# balance_stm32.net
KiCad netlist of a schematic drawn in EasyEDA Pro
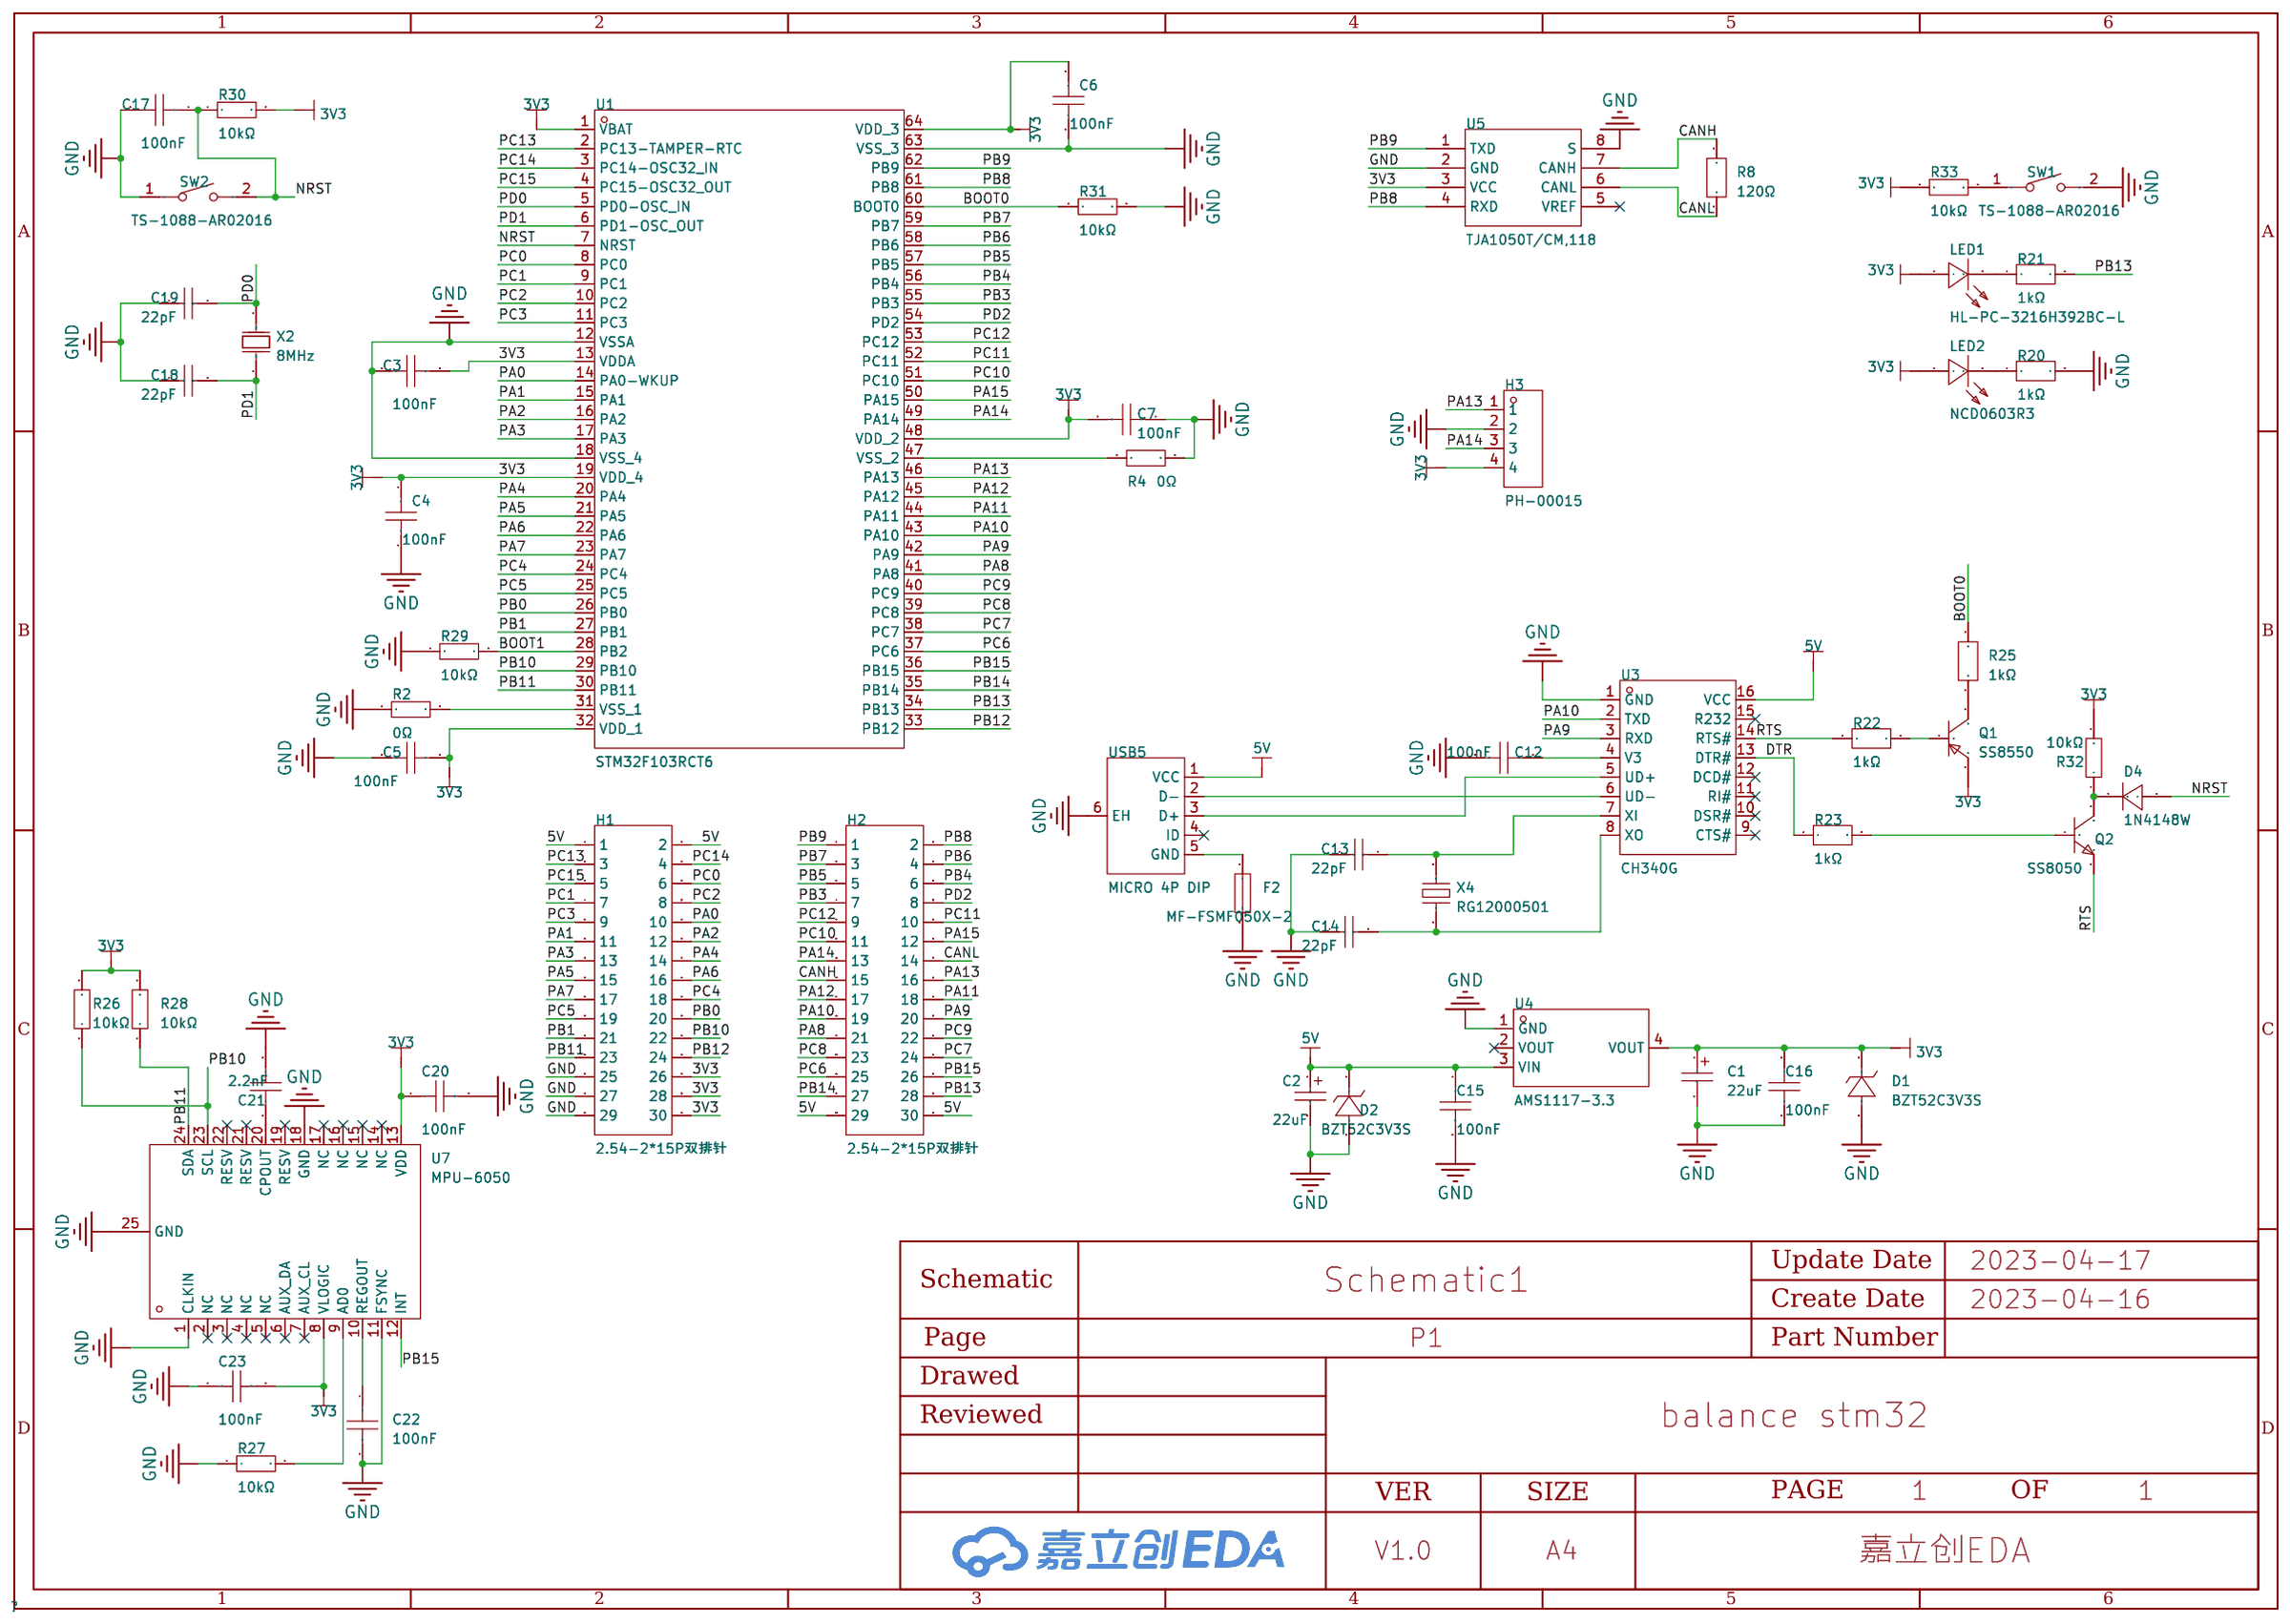
[diagram p0: schematic sheet]

(export (version "E")
  (design (tool "Eeschema 10.0.6"))
  (components
    (comp (ref "C1")
      (value "22uF")
      (footprint "easyedapro:CAP-SMD_L7.3-W4.3-RD")
      (description "容值:22uF;精度:±10%;额定电压:35V;等效串联电阻:900mΩ@100kHz;")
      (fields (field (name "Manufacturer Part") "TAJD226K035RNJ") (field (name "Manufacturer") "Kyocera AVX"))
      (libsource (lib "easyedapro") (part "TAJD226K035RNJ"))
    )
    (comp (ref "C2")
      (value "22uF")
      (footprint "easyedapro:CAP-SMD_L7.3-W4.3-RD")
      (description "容值:22uF;精度:±10%;额定电压:35V;等效串联电阻:900mΩ@100kHz;")
      (fields (field (name "Manufacturer Part") "TAJD226K035RNJ") (field (name "Manufacturer") "Kyocera AVX"))
      (libsource (lib "easyedapro") (part "TAJD226K035RNJ"))
    )
    (comp (ref "C3")
      (value "100nF")
      (footprint "easyedapro:C0603")
      (description "容值:100nF;精度:±10%;额定电压:50V;材质(温度系数):X7R;")
      (fields
        (field (name "Manufacturer Part") "CL10B104KB8NNNC")
        (field (name "Manufacturer") "SAMSUNG(三星)")
      )
      (libsource (lib "easyedapro") (part "CL10B104KB8NNNC"))
    )
    (comp (ref "C4")
      (value "100nF")
      (footprint "easyedapro:C0603")
      (description "容值:100nF;精度:±10%;额定电压:50V;材质(温度系数):X7R;")
      (fields
        (field (name "Manufacturer Part") "CL10B104KB8NNNC")
        (field (name "Manufacturer") "SAMSUNG(三星)")
      )
      (libsource (lib "easyedapro") (part "CL10B104KB8NNNC"))
    )
    (comp (ref "C5")
      (value "100nF")
      (footprint "easyedapro:C0603")
      (description "容值:100nF;精度:±10%;额定电压:50V;材质(温度系数):X7R;")
      (fields
        (field (name "Manufacturer Part") "CL10B104KB8NNNC")
        (field (name "Manufacturer") "SAMSUNG(三星)")
      )
      (libsource (lib "easyedapro") (part "CL10B104KB8NNNC"))
    )
    (comp (ref "C6")
      (value "100nF")
      (footprint "easyedapro:C0603")
      (description "容值:100nF;精度:±10%;额定电压:50V;材质(温度系数):X7R;")
      (fields
        (field (name "Manufacturer Part") "CL10B104KB8NNNC")
        (field (name "Manufacturer") "SAMSUNG(三星)")
      )
      (libsource (lib "easyedapro") (part "CL10B104KB8NNNC"))
    )
    (comp (ref "C7")
      (value "100nF")
      (footprint "easyedapro:C0603")
      (description "容值:100nF;精度:±10%;额定电压:50V;材质(温度系数):X7R;")
      (fields
        (field (name "Manufacturer Part") "CL10B104KB8NNNC")
        (field (name "Manufacturer") "SAMSUNG(三星)")
      )
      (libsource (lib "easyedapro") (part "CL10B104KB8NNNC"))
    )
    (comp (ref "C12")
      (value "100nF")
      (footprint "easyedapro:C0603")
      (description "容值:100nF;精度:±10%;额定电压:50V;材质(温度系数):X7R;")
      (fields
        (field (name "Manufacturer Part") "CL10B104KB8NNNC")
        (field (name "Manufacturer") "SAMSUNG(三星)")
      )
      (libsource (lib "easyedapro") (part "CL10B104KB8NNNC"))
    )
    (comp (ref "C13")
      (value "22pF")
      (footprint "easyedapro:C0603")
      (description "容值:22pF;精度:±5%;额定电压:50V;材质(温度系数):C0G;")
      (fields
        (field (name "Manufacturer Part") "CL10C220JB8NNNC")
        (field (name "Manufacturer") "SAMSUNG(三星)")
      )
      (libsource (lib "easyedapro") (part "CL10C220JB8NNNC"))
    )
    (comp (ref "C14")
      (value "22pF")
      (footprint "easyedapro:C0603")
      (description "容值:22pF;精度:±5%;额定电压:50V;材质(温度系数):C0G;")
      (fields
        (field (name "Manufacturer Part") "CL10C220JB8NNNC")
        (field (name "Manufacturer") "SAMSUNG(三星)")
      )
      (libsource (lib "easyedapro") (part "CL10C220JB8NNNC"))
    )
    (comp (ref "C15")
      (value "100nF")
      (footprint "easyedapro:C0603")
      (description "容值:100nF;精度:±10%;额定电压:50V;材质(温度系数):X7R;")
      (fields
        (field (name "Manufacturer Part") "CL10B104KB8NNNC")
        (field (name "Manufacturer") "SAMSUNG(三星)")
      )
      (libsource (lib "easyedapro") (part "CL10B104KB8NNNC"))
    )
    (comp (ref "C16")
      (value "100nF")
      (footprint "easyedapro:C0603")
      (description "容值:100nF;精度:±10%;额定电压:50V;材质(温度系数):X7R;")
      (fields
        (field (name "Manufacturer Part") "CL10B104KB8NNNC")
        (field (name "Manufacturer") "SAMSUNG(三星)")
      )
      (libsource (lib "easyedapro") (part "CL10B104KB8NNNC"))
    )
    (comp (ref "C17")
      (value "100nF")
      (footprint "easyedapro:C0603")
      (description "容值:100nF;精度:±10%;额定电压:50V;材质(温度系数):X7R;")
      (fields
        (field (name "Manufacturer Part") "CL10B104KB8NNNC")
        (field (name "Manufacturer") "SAMSUNG(三星)")
      )
      (libsource (lib "easyedapro") (part "CL10B104KB8NNNC"))
    )
    (comp (ref "C18")
      (value "22pF")
      (footprint "easyedapro:C0603")
      (description "容值:22pF;精度:±5%;额定电压:50V;材质(温度系数):C0G;")
      (fields
        (field (name "Manufacturer Part") "CL10C220JB8NNNC")
        (field (name "Manufacturer") "SAMSUNG(三星)")
      )
      (libsource (lib "easyedapro") (part "CL10C220JB8NNNC"))
    )
    (comp (ref "C19")
      (value "22pF")
      (footprint "easyedapro:C0603")
      (description "容值:22pF;精度:±5%;额定电压:50V;材质(温度系数):C0G;")
      (fields
        (field (name "Manufacturer Part") "CL10C220JB8NNNC")
        (field (name "Manufacturer") "SAMSUNG(三星)")
      )
      (libsource (lib "easyedapro") (part "CL10C220JB8NNNC"))
    )
    (comp (ref "C20")
      (value "100nF")
      (footprint "easyedapro:C0603")
      (description "容值:100nF;精度:±10%;额定电压:50V;材质(温度系数):X7R;")
      (fields
        (field (name "Manufacturer Part") "CL10B104KB8NNNC")
        (field (name "Manufacturer") "SAMSUNG(三星)")
      )
      (libsource (lib "easyedapro") (part "CL10B104KB8NNNC"))
    )
    (comp (ref "C21")
      (value "2.2nF")
      (footprint "easyedapro:C0603")
      (description "容值:2.2nF;精度:±5%;额定电压:250V;材质(温度系数):C0G;")
      (fields (field (name "Manufacturer Part") "C1608C0G2E222JT000N") (field (name "Manufacturer") "TDK"))
      (libsource (lib "easyedapro") (part "C1608C0G2E222JT000N"))
    )
    (comp (ref "C22")
      (value "100nF")
      (footprint "easyedapro:C0603")
      (description "容值:100nF;精度:±10%;额定电压:50V;材质(温度系数):X7R;")
      (fields
        (field (name "Manufacturer Part") "CL10B104KB8NNNC")
        (field (name "Manufacturer") "SAMSUNG(三星)")
      )
      (libsource (lib "easyedapro") (part "CL10B104KB8NNNC"))
    )
    (comp (ref "C23")
      (value "100nF")
      (footprint "easyedapro:C0603")
      (description "容值:100nF;精度:±10%;额定电压:50V;材质(温度系数):X7R;")
      (fields
        (field (name "Manufacturer Part") "CL10B104KB8NNNC")
        (field (name "Manufacturer") "SAMSUNG(三星)")
      )
      (libsource (lib "easyedapro") (part "CL10B104KB8NNNC"))
    )
    (comp (ref "D1")
      (value "BZT52C3V3S")
      (footprint "easyedapro:SOD-323_L1.7-W1.3-LS2.6-RD-1")
      (description "二极管配置:-;稳压值(标称值):3.3V;稳压值(范围):3.3V~3.5V;功率:200mW;反向电流(Ir):5uA@1V;阻抗(Zzt):95Ω;")
      (fields (field (name "Manufacturer") "YONGYUTAI(永裕泰)"))
      (libsource (lib "easyedapro") (part "BZT52C3V3S_C2892655"))
    )
    (comp (ref "D2")
      (value "BZT52C3V3S")
      (footprint "easyedapro:SOD-323_L1.7-W1.3-LS2.6-RD-1")
      (description "二极管配置:-;稳压值(标称值):3.3V;稳压值(范围):3.3V~3.5V;功率:200mW;反向电流(Ir):5uA@1V;阻抗(Zzt):95Ω;")
      (fields (field (name "Manufacturer") "YONGYUTAI(永裕泰)"))
      (libsource (lib "easyedapro") (part "BZT52C3V3S_C2892655"))
    )
    (comp (ref "D4")
      (value "1N4148W")
      (footprint "easyedapro:SOD-123_L2.8-W1.8-LS3.7-RD")
      (fields (field (name "Manufacturer") "Slkor(萨科微)"))
      (libsource (lib "easyedapro") (part "1N4148W_C444720"))
    )
    (comp (ref "F2")
      (value "MF-FSMF050X-2")
      (footprint "easyedapro:F0603")
      (fields (field (name "Manufacturer") "BOURNS"))
      (libsource (lib "easyedapro") (part "MF-FSMF050X-2"))
    )
    (comp (ref "H1")
      (value "2.54-2*15P双排针")
      (footprint "easyedapro:HDR-TH_30P-P2.54-V-M-R2-C15-S2.54")
      (fields (field (name "Manufacturer") "BOOMELE(博穆精密)"))
      (libsource (lib "easyedapro") (part "Header-Male-2.54_2x15"))
    )
    (comp (ref "H2")
      (value "2.54-2*15P双排针")
      (footprint "easyedapro:HDR-TH_30P-P2.54-V-M-R2-C15-S2.54")
      (fields (field (name "Manufacturer") "BOOMELE(博穆精密)"))
      (libsource (lib "easyedapro") (part "Header-Male-2.54_2x15"))
    )
    (comp (ref "H3")
      (value "PH-00015")
      (footprint "easyedapro:HDR-TH_4P-P2.54-V-M")
      (fields (field (name "Manufacturer") "Liansheng(连盛)"))
      (libsource (lib "easyedapro") (part "PH-00015"))
    )
    (comp (ref "LED1")
      (value "HL-PC-3216H392BC-L")
      (footprint "easyedapro:LED1206-R-RD_BLUE")
      (fields (field (name "Manufacturer") "HONGLITRONIC(鸿利光电)"))
      (libsource (lib "easyedapro") (part "HL-PC-3216H392BC-L"))
    )
    (comp (ref "LED2")
      (value "NCD0603R3")
      (footprint "easyedapro:LED0603-R-RD_RED")
      (description "尺寸1.6x0.8x0.8；IF=20ma：1.6~2.6v，620~640nm,51~150mcd金线，光强高，功耗低，可靠性好，寿命长")
      (fields (field (name "Manufacturer") "国星光电"))
      (libsource (lib "easyedapro") (part "NCD0603R3"))
    )
    (comp (ref "Q1")
      (value "SS8550")
      (footprint "easyedapro:SOT-23-3_L2.9-W1.3-P1.90-LS2.4-BR")
      (fields (field (name "Manufacturer") "FUXINSEMI(富芯森美)"))
      (libsource (lib "easyedapro") (part "SS8550_C908251"))
    )
    (comp (ref "Q2")
      (value "SS8050")
      (footprint "easyedapro:SOT-23-3_L2.9-W1.3-P1.90-LS2.4-BR")
      (fields (field (name "Manufacturer") "FUXINSEMI(富芯森美)"))
      (libsource (lib "easyedapro") (part "SS8050"))
    )
    (comp (ref "R2")
      (value "0Ω")
      (footprint "easyedapro:R0603")
      (description "电阻类型:厚膜电阻;阻值:0Ω;精度:-;功率:250mW;")
      (fields (field (name "Manufacturer Part") "PMR03EZPJ000") (field (name "Manufacturer") "ROHM(罗姆)"))
      (libsource (lib "easyedapro") (part "PMR03EZPJ000"))
    )
    (comp (ref "R4")
      (value "0Ω")
      (footprint "easyedapro:R0603")
      (description "电阻类型:厚膜电阻;阻值:0Ω;精度:-;功率:250mW;")
      (fields (field (name "Manufacturer Part") "PMR03EZPJ000") (field (name "Manufacturer") "ROHM(罗姆)"))
      (libsource (lib "easyedapro") (part "PMR03EZPJ000"))
    )
    (comp (ref "R8")
      (value "120Ω")
      (footprint "easyedapro:R0805")
      (description "电阻类型:薄膜电阻;阻值:120Ω;精度:±0.1%;功率:200mW;")
      (fields
        (field (name "Manufacturer Part") "RTAN0805BKE120R")
        (field (name "Manufacturer") "SEI(Stackpole Electronics Inc.)")
      )
      (libsource (lib "easyedapro") (part "RTAN0805BKE120R"))
    )
    (comp (ref "R20")
      (value "1kΩ")
      (footprint "easyedapro:R0603")
      (description "电阻类型:薄膜电阻;阻值:1kΩ;精度:±0.1%;功率:100mW;")
      (fields (field (name "Manufacturer Part") "ERA3VEB1001V") (field (name "Manufacturer") "PANASONIC(松下)"))
      (libsource (lib "easyedapro") (part "ERA3VEB1001V"))
    )
    (comp (ref "R21")
      (value "1kΩ")
      (footprint "easyedapro:R0603")
      (description "电阻类型:薄膜电阻;阻值:1kΩ;精度:±0.1%;功率:100mW;")
      (fields (field (name "Manufacturer Part") "ERA3VEB1001V") (field (name "Manufacturer") "PANASONIC(松下)"))
      (libsource (lib "easyedapro") (part "ERA3VEB1001V"))
    )
    (comp (ref "R22")
      (value "1kΩ")
      (footprint "easyedapro:R0603")
      (description "电阻类型:薄膜电阻;阻值:1kΩ;精度:±0.1%;功率:100mW;")
      (fields (field (name "Manufacturer Part") "ERA3VEB1001V") (field (name "Manufacturer") "PANASONIC(松下)"))
      (libsource (lib "easyedapro") (part "ERA3VEB1001V"))
    )
    (comp (ref "R23")
      (value "1kΩ")
      (footprint "easyedapro:R0603")
      (description "电阻类型:薄膜电阻;阻值:1kΩ;精度:±0.1%;功率:100mW;")
      (fields (field (name "Manufacturer Part") "ERA3VEB1001V") (field (name "Manufacturer") "PANASONIC(松下)"))
      (libsource (lib "easyedapro") (part "ERA3VEB1001V"))
    )
    (comp (ref "R25")
      (value "1kΩ")
      (footprint "easyedapro:R0603")
      (description "电阻类型:薄膜电阻;阻值:1kΩ;精度:±0.1%;功率:100mW;")
      (fields (field (name "Manufacturer Part") "ERA3VEB1001V") (field (name "Manufacturer") "PANASONIC(松下)"))
      (libsource (lib "easyedapro") (part "ERA3VEB1001V"))
    )
    (comp (ref "R26")
      (value "10kΩ")
      (footprint "easyedapro:R0603")
      (description "电阻类型:厚膜电阻;阻值:10kΩ;精度:±0.1%;功率:200mW;")
      (fields (field (name "Manufacturer Part") "ERJPB3B1002V") (field (name "Manufacturer") "PANASONIC(松下)"))
      (libsource (lib "easyedapro") (part "ERJPB3B1002V"))
    )
    (comp (ref "R27")
      (value "10kΩ")
      (footprint "easyedapro:R0603")
      (description "电阻类型:厚膜电阻;阻值:10kΩ;精度:±0.1%;功率:200mW;")
      (fields (field (name "Manufacturer Part") "ERJPB3B1002V") (field (name "Manufacturer") "PANASONIC(松下)"))
      (libsource (lib "easyedapro") (part "ERJPB3B1002V"))
    )
    (comp (ref "R28")
      (value "10kΩ")
      (footprint "easyedapro:R0603")
      (description "电阻类型:厚膜电阻;阻值:10kΩ;精度:±0.1%;功率:200mW;")
      (fields (field (name "Manufacturer Part") "ERJPB3B1002V") (field (name "Manufacturer") "PANASONIC(松下)"))
      (libsource (lib "easyedapro") (part "ERJPB3B1002V"))
    )
    (comp (ref "R29")
      (value "10kΩ")
      (footprint "easyedapro:R0603")
      (description "电阻类型:厚膜电阻;阻值:10kΩ;精度:±0.1%;功率:200mW;")
      (fields (field (name "Manufacturer Part") "ERJPB3B1002V") (field (name "Manufacturer") "PANASONIC(松下)"))
      (libsource (lib "easyedapro") (part "ERJPB3B1002V"))
    )
    (comp (ref "R30")
      (value "10kΩ")
      (footprint "easyedapro:R0603")
      (description "电阻类型:厚膜电阻;阻值:10kΩ;精度:±0.1%;功率:200mW;")
      (fields (field (name "Manufacturer Part") "ERJPB3B1002V") (field (name "Manufacturer") "PANASONIC(松下)"))
      (libsource (lib "easyedapro") (part "ERJPB3B1002V"))
    )
    (comp (ref "R31")
      (value "10kΩ")
      (footprint "easyedapro:R0603")
      (description "电阻类型:厚膜电阻;阻值:10kΩ;精度:±0.1%;功率:200mW;")
      (fields (field (name "Manufacturer Part") "ERJPB3B1002V") (field (name "Manufacturer") "PANASONIC(松下)"))
      (libsource (lib "easyedapro") (part "ERJPB3B1002V"))
    )
    (comp (ref "R32")
      (value "10kΩ")
      (footprint "easyedapro:R0603")
      (description "电阻类型:厚膜电阻;阻值:10kΩ;精度:±0.1%;功率:200mW;")
      (fields (field (name "Manufacturer Part") "ERJPB3B1002V") (field (name "Manufacturer") "PANASONIC(松下)"))
      (libsource (lib "easyedapro") (part "ERJPB3B1002V"))
    )
    (comp (ref "R33")
      (value "10kΩ")
      (footprint "easyedapro:R0603")
      (description "电阻类型:厚膜电阻;阻值:10kΩ;精度:±0.1%;功率:200mW;")
      (fields (field (name "Manufacturer Part") "ERJPB3B1002V") (field (name "Manufacturer") "PANASONIC(松下)"))
      (libsource (lib "easyedapro") (part "ERJPB3B1002V"))
    )
    (comp (ref "SW1")
      (value "TS-1088-AR02016")
      (footprint "easyedapro:SW-SMD_L3.9-W3.0-P4.45")
      (description "触点电流:50mA;额定电压(DC):12V;绝缘电阻:100MΩ;电路结构:单刀单掷;安装方式:立贴;作用力:160gf@±50gf;机械寿命:10万次;带支架:否;")
      (fields (field (name "Manufacturer") "XUNPU(讯普)"))
      (libsource (lib "easyedapro") (part "TS-1088-AR02016"))
    )
    (comp (ref "SW2")
      (value "TS-1088-AR02016")
      (footprint "easyedapro:SW-SMD_L3.9-W3.0-P4.45")
      (description "触点电流:50mA;额定电压(DC):12V;绝缘电阻:100MΩ;电路结构:单刀单掷;安装方式:立贴;作用力:160gf@±50gf;机械寿命:10万次;带支架:否;")
      (fields (field (name "Manufacturer") "XUNPU(讯普)"))
      (libsource (lib "easyedapro") (part "TS-1088-AR02016"))
    )
    (comp (ref "U1")
      (value "STM32F103RCT6")
      (footprint "easyedapro:LQFP-64_L10.0-W10.0-P0.50-LS12.0-BL")
      (fields (field (name "Manufacturer") "ST(意法半导体)"))
      (libsource (lib "easyedapro") (part "STM32F103RCT6"))
    )
    (comp (ref "U3")
      (value "CH340G")
      (footprint "easyedapro:SOIC-16_L9.9-W3.9-P1.27-LS6.0-BL")
      (description "类型:Transceiver;协议类别:USB 2.0;驱动器/接收器数:-;数据速率:2Mbps;")
      (fields (field (name "Manufacturer") "WCH(南京沁恒)"))
      (libsource (lib "easyedapro") (part "CH340G"))
    )
    (comp (ref "U4")
      (value "AMS1117-3.3")
      (footprint "easyedapro:SOT-223-3_L6.5-W3.4-P2.30-LS7.0-BR")
      (description "输出类型:固定;输出极性:正;最大输入电压:-;输出电压:3.3V;输出电流:1A;电源纹波抑制比(PSRR):72dB@(120Hz);")
      (fields (field (name "Manufacturer") "AMS"))
      (libsource (lib "easyedapro") (part "AMS1117-3.3"))
    )
    (comp (ref "U5")
      (value "TJA1050T/CM,118")
      (footprint "easyedapro:SOIC-8_L5.0-W4.0-P1.27-LS6.0-BL")
      (description "类型:收发器;")
      (fields (field (name "Manufacturer") "NXP(恩智浦)"))
      (libsource (lib "easyedapro") (part "TJA1050T/CM,118"))
    )
    (comp (ref "U7")
      (value "MPU-6050")
      (footprint "easyedapro:QFN-24_L4.0-W4.0-P0.50-BL-EP2.7")
      (description "三轴加速度计和三轴陀螺仪，工作电压：2.375V~3.46V")
      (fields (field (name "Manufacturer") "TDK InvenSense(应美盛)"))
      (libsource (lib "easyedapro") (part "MPU-6050_C24112"))
    )
    (comp (ref "USB5")
      (value "MICRO 4P DIP")
      (footprint "easyedapro:MINI-USB-SMD_MICRO-4P-DIP")
      (description "连接器类型:Micro-B;标准:USB 2.0;公母:母座;触点数量:4;端口数量:1;安装方式:卧贴;额定电流 - 电源:1A;工作温度范围:-30°C~+80°C;")
      (fields (field (name "Manufacturer") "SHOU HAN(首韩)"))
      (libsource (lib "easyedapro") (part "MICRO 4P DIP"))
    )
    (comp (ref "X2")
      (value "8MHz")
      (footprint "easyedapro:CRYSTAL-SMD_L5.0-W3.2")
      (description "频率:8MHz;频率公差:±10ppm;频率稳定度:±50ppm;负载电容:20pF;")
      (fields (field (name "Manufacturer Part") "X50328MSB2GI") (field (name "Manufacturer") "YXC(扬兴晶振)"))
      (libsource (lib "easyedapro") (part "X50328MSB2GI"))
    )
    (comp (ref "X4")
      (value "RG12000501")
      (footprint "easyedapro:CRYSTAL-SMD_L5.0-W3.2")
      (description "GLASS5032-2P")
      (fields (field (name "Manufacturer") "TROQ(创捷)"))
      (libsource (lib "easyedapro") (part "RG12000501"))
    )
  )
  (nets
    (net (code "1") (name "/BOOT0") (class "Default")
      (node (ref "R25") (pin "2") (pinfunction "2_2") (pintype "input"))
      (node (ref "R31") (pin "1") (pinfunction "1_1") (pintype "input"))
      (node (ref "U1") (pin "60") (pinfunction "BOOT0_60") (pintype "input"))
    )
    (net (code "2") (name "/BOOT1") (class "Default")
      (node (ref "R29") (pin "2") (pinfunction "2_2") (pintype "input"))
      (node (ref "U1") (pin "28") (pinfunction "PB2_28") (pintype "input"))
    )
    (net (code "3") (name "/CANH") (class "Default")
      (node (ref "H2") (pin "15") (pinfunction "15_15") (pintype "input"))
      (node (ref "R8") (pin "2") (pinfunction "2_2") (pintype "input"))
      (node (ref "U5") (pin "7") (pinfunction "CANH_7") (pintype "input"))
    )
    (net (code "4") (name "/CANL") (class "Default")
      (node (ref "H2") (pin "14") (pinfunction "14_14") (pintype "input"))
      (node (ref "R8") (pin "1") (pinfunction "1_1") (pintype "input"))
      (node (ref "U5") (pin "6") (pinfunction "CANL_6") (pintype "input"))
    )
    (net (code "5") (name "/DTR") (class "Default")
      (node (ref "R23") (pin "1") (pinfunction "1_1") (pintype "input"))
      (node (ref "U3") (pin "13") (pinfunction "DTR#_13") (pintype "input"))
    )
    (net (code "6") (name "/NRST") (class "Default")
      (node (ref "C17") (pin "1") (pinfunction "1_1") (pintype "input"))
      (node (ref "D4") (pin "2") (pinfunction "A_2") (pintype "input"))
      (node (ref "R30") (pin "1") (pinfunction "1_1") (pintype "input"))
      (node (ref "SW2") (pin "2") (pinfunction "2_2") (pintype "input"))
      (node (ref "U1") (pin "7") (pinfunction "NRST_7") (pintype "input"))
    )
    (net (code "7") (name "/PA0") (class "Default")
      (node (ref "H1") (pin "10") (pinfunction "10_10") (pintype "input"))
      (node (ref "U1") (pin "14") (pinfunction "PA0-WKUP_14") (pintype "input"))
    )
    (net (code "8") (name "/PA1") (class "Default")
      (node (ref "H1") (pin "11") (pinfunction "11_11") (pintype "input"))
      (node (ref "U1") (pin "15") (pinfunction "PA1_15") (pintype "input"))
    )
    (net (code "9") (name "/PA2") (class "Default")
      (node (ref "H1") (pin "12") (pinfunction "12_12") (pintype "input"))
      (node (ref "U1") (pin "16") (pinfunction "PA2_16") (pintype "input"))
    )
    (net (code "10") (name "/PA3") (class "Default")
      (node (ref "H1") (pin "13") (pinfunction "13_13") (pintype "input"))
      (node (ref "U1") (pin "17") (pinfunction "PA3_17") (pintype "input"))
    )
    (net (code "11") (name "/PA4") (class "Default")
      (node (ref "H1") (pin "14") (pinfunction "14_14") (pintype "input"))
      (node (ref "U1") (pin "20") (pinfunction "PA4_20") (pintype "input"))
    )
    (net (code "12") (name "/PA5") (class "Default")
      (node (ref "H1") (pin "15") (pinfunction "15_15") (pintype "input"))
      (node (ref "U1") (pin "21") (pinfunction "PA5_21") (pintype "input"))
    )
    (net (code "13") (name "/PA6") (class "Default")
      (node (ref "H1") (pin "16") (pinfunction "16_16") (pintype "input"))
      (node (ref "U1") (pin "22") (pinfunction "PA6_22") (pintype "input"))
    )
    (net (code "14") (name "/PA7") (class "Default")
      (node (ref "H1") (pin "17") (pinfunction "17_17") (pintype "input"))
      (node (ref "U1") (pin "23") (pinfunction "PA7_23") (pintype "input"))
    )
    (net (code "15") (name "/PA8") (class "Default")
      (node (ref "H2") (pin "21") (pinfunction "21_21") (pintype "input"))
      (node (ref "U1") (pin "41") (pinfunction "PA8_41") (pintype "input"))
    )
    (net (code "16") (name "/PA9") (class "Default")
      (node (ref "H2") (pin "20") (pinfunction "20_20") (pintype "input"))
      (node (ref "U1") (pin "42") (pinfunction "PA9_42") (pintype "input"))
      (node (ref "U3") (pin "3") (pinfunction "RXD_3") (pintype "input"))
    )
    (net (code "17") (name "/PA10") (class "Default")
      (node (ref "H2") (pin "19") (pinfunction "19_19") (pintype "input"))
      (node (ref "U1") (pin "43") (pinfunction "PA10_43") (pintype "input"))
      (node (ref "U3") (pin "2") (pinfunction "TXD_2") (pintype "input"))
    )
    (net (code "18") (name "/PA11") (class "Default")
      (node (ref "H2") (pin "18") (pinfunction "18_18") (pintype "input"))
      (node (ref "U1") (pin "44") (pinfunction "PA11_44") (pintype "input"))
    )
    (net (code "19") (name "/PA12") (class "Default")
      (node (ref "H2") (pin "17") (pinfunction "17_17") (pintype "input"))
      (node (ref "U1") (pin "45") (pinfunction "PA12_45") (pintype "input"))
    )
    (net (code "20") (name "/PA13") (class "Default")
      (node (ref "H2") (pin "16") (pinfunction "16_16") (pintype "input"))
      (node (ref "H3") (pin "1") (pinfunction "1_1") (pintype "input"))
      (node (ref "U1") (pin "46") (pinfunction "PA13_46") (pintype "input"))
    )
    (net (code "21") (name "/PA14") (class "Default")
      (node (ref "H2") (pin "13") (pinfunction "13_13") (pintype "input"))
      (node (ref "H3") (pin "3") (pinfunction "3_3") (pintype "input"))
      (node (ref "U1") (pin "49") (pinfunction "PA14_49") (pintype "input"))
    )
    (net (code "22") (name "/PA15") (class "Default")
      (node (ref "H2") (pin "12") (pinfunction "12_12") (pintype "input"))
      (node (ref "U1") (pin "50") (pinfunction "PA15_50") (pintype "input"))
    )
    (net (code "23") (name "/PB0") (class "Default")
      (node (ref "H1") (pin "20") (pinfunction "20_20") (pintype "input"))
      (node (ref "U1") (pin "26") (pinfunction "PB0_26") (pintype "input"))
    )
    (net (code "24") (name "/PB1") (class "Default")
      (node (ref "H1") (pin "21") (pinfunction "21_21") (pintype "input"))
      (node (ref "U1") (pin "27") (pinfunction "PB1_27") (pintype "input"))
    )
    (net (code "25") (name "/PB3") (class "Default")
      (node (ref "H2") (pin "7") (pinfunction "7_7") (pintype "input"))
      (node (ref "U1") (pin "55") (pinfunction "PB3_55") (pintype "input"))
    )
    (net (code "26") (name "/PB4") (class "Default")
      (node (ref "H2") (pin "6") (pinfunction "6_6") (pintype "input"))
      (node (ref "U1") (pin "56") (pinfunction "PB4_56") (pintype "input"))
    )
    (net (code "27") (name "/PB5") (class "Default")
      (node (ref "H2") (pin "5") (pinfunction "5_5") (pintype "input"))
      (node (ref "U1") (pin "57") (pinfunction "PB5_57") (pintype "input"))
    )
    (net (code "28") (name "/PB6") (class "Default")
      (node (ref "H2") (pin "4") (pinfunction "4_4") (pintype "input"))
      (node (ref "U1") (pin "58") (pinfunction "PB6_58") (pintype "input"))
    )
    (net (code "29") (name "/PB7") (class "Default")
      (node (ref "H2") (pin "3") (pinfunction "3_3") (pintype "input"))
      (node (ref "U1") (pin "59") (pinfunction "PB7_59") (pintype "input"))
    )
    (net (code "30") (name "/PB8") (class "Default")
      (node (ref "H2") (pin "2") (pinfunction "2_2") (pintype "input"))
      (node (ref "U1") (pin "61") (pinfunction "PB8_61") (pintype "input"))
      (node (ref "U5") (pin "4") (pinfunction "RXD_4") (pintype "input"))
    )
    (net (code "31") (name "/PB9") (class "Default")
      (node (ref "H2") (pin "1") (pinfunction "1_1") (pintype "input"))
      (node (ref "U1") (pin "62") (pinfunction "PB9_62") (pintype "input"))
      (node (ref "U5") (pin "1") (pinfunction "TXD_1") (pintype "input"))
    )
    (net (code "32") (name "/PB10") (class "Default")
      (node (ref "H1") (pin "22") (pinfunction "22_22") (pintype "input"))
      (node (ref "R26") (pin "1") (pinfunction "1_1") (pintype "input"))
      (node (ref "U1") (pin "29") (pinfunction "PB10_29") (pintype "input"))
      (node (ref "U7") (pin "23") (pinfunction "SCL_23") (pintype "input"))
    )
    (net (code "33") (name "/PB11") (class "Default")
      (node (ref "H1") (pin "23") (pinfunction "23_23") (pintype "input"))
      (node (ref "R28") (pin "1") (pinfunction "1_1") (pintype "input"))
      (node (ref "U1") (pin "30") (pinfunction "PB11_30") (pintype "input"))
      (node (ref "U7") (pin "24") (pinfunction "SDA_24") (pintype "input"))
    )
    (net (code "34") (name "/PB12") (class "Default")
      (node (ref "H1") (pin "24") (pinfunction "24_24") (pintype "input"))
      (node (ref "U1") (pin "33") (pinfunction "PB12_33") (pintype "input"))
    )
    (net (code "35") (name "/PB13") (class "Default")
      (node (ref "H2") (pin "28") (pinfunction "28_28") (pintype "input"))
      (node (ref "R21") (pin "2") (pinfunction "2_2") (pintype "input"))
      (node (ref "U1") (pin "34") (pinfunction "PB13_34") (pintype "input"))
    )
    (net (code "36") (name "/PB14") (class "Default")
      (node (ref "H2") (pin "27") (pinfunction "27_27") (pintype "input"))
      (node (ref "U1") (pin "35") (pinfunction "PB14_35") (pintype "input"))
    )
    (net (code "37") (name "/PB15") (class "Default")
      (node (ref "H2") (pin "26") (pinfunction "26_26") (pintype "input"))
      (node (ref "U1") (pin "36") (pinfunction "PB15_36") (pintype "input"))
      (node (ref "U7") (pin "12") (pinfunction "INT_12") (pintype "input"))
    )
    (net (code "38") (name "/PC0") (class "Default")
      (node (ref "H1") (pin "6") (pinfunction "6_6") (pintype "input"))
      (node (ref "U1") (pin "8") (pinfunction "PC0_8") (pintype "input"))
    )
    (net (code "39") (name "/PC1") (class "Default")
      (node (ref "H1") (pin "7") (pinfunction "7_7") (pintype "input"))
      (node (ref "U1") (pin "9") (pinfunction "PC1_9") (pintype "input"))
    )
    (net (code "40") (name "/PC2") (class "Default")
      (node (ref "H1") (pin "8") (pinfunction "8_8") (pintype "input"))
      (node (ref "U1") (pin "10") (pinfunction "PC2_10") (pintype "input"))
    )
    (net (code "41") (name "/PC3") (class "Default")
      (node (ref "H1") (pin "9") (pinfunction "9_9") (pintype "input"))
      (node (ref "U1") (pin "11") (pinfunction "PC3_11") (pintype "input"))
    )
    (net (code "42") (name "/PC4") (class "Default")
      (node (ref "H1") (pin "18") (pinfunction "18_18") (pintype "input"))
      (node (ref "U1") (pin "24") (pinfunction "PC4_24") (pintype "input"))
    )
    (net (code "43") (name "/PC5") (class "Default")
      (node (ref "H1") (pin "19") (pinfunction "19_19") (pintype "input"))
      (node (ref "U1") (pin "25") (pinfunction "PC5_25") (pintype "input"))
    )
    (net (code "44") (name "/PC6") (class "Default")
      (node (ref "H2") (pin "25") (pinfunction "25_25") (pintype "input"))
      (node (ref "U1") (pin "37") (pinfunction "PC6_37") (pintype "input"))
    )
    (net (code "45") (name "/PC7") (class "Default")
      (node (ref "H2") (pin "24") (pinfunction "24_24") (pintype "input"))
      (node (ref "U1") (pin "38") (pinfunction "PC7_38") (pintype "input"))
    )
    (net (code "46") (name "/PC8") (class "Default")
      (node (ref "H2") (pin "23") (pinfunction "23_23") (pintype "input"))
      (node (ref "U1") (pin "39") (pinfunction "PC8_39") (pintype "input"))
    )
    (net (code "47") (name "/PC9") (class "Default")
      (node (ref "H2") (pin "22") (pinfunction "22_22") (pintype "input"))
      (node (ref "U1") (pin "40") (pinfunction "PC9_40") (pintype "input"))
    )
    (net (code "48") (name "/PC10") (class "Default")
      (node (ref "H2") (pin "11") (pinfunction "11_11") (pintype "input"))
      (node (ref "U1") (pin "51") (pinfunction "PC10_51") (pintype "input"))
    )
    (net (code "49") (name "/PC11") (class "Default")
      (node (ref "H2") (pin "10") (pinfunction "10_10") (pintype "input"))
      (node (ref "U1") (pin "52") (pinfunction "PC11_52") (pintype "input"))
    )
    (net (code "50") (name "/PC12") (class "Default")
      (node (ref "H2") (pin "9") (pinfunction "9_9") (pintype "input"))
      (node (ref "U1") (pin "53") (pinfunction "PC12_53") (pintype "input"))
    )
    (net (code "51") (name "/PC13") (class "Default")
      (node (ref "H1") (pin "3") (pinfunction "3_3") (pintype "input"))
      (node (ref "U1") (pin "2") (pinfunction "PC13-TAMPER-RTC_2") (pintype "input"))
    )
    (net (code "52") (name "/PC14") (class "Default")
      (node (ref "H1") (pin "4") (pinfunction "4_4") (pintype "input"))
      (node (ref "U1") (pin "3") (pinfunction "PC14-OSC32_IN_3") (pintype "input"))
    )
    (net (code "53") (name "/PC15") (class "Default")
      (node (ref "H1") (pin "5") (pinfunction "5_5") (pintype "input"))
      (node (ref "U1") (pin "4") (pinfunction "PC15-OSC32_OUT_4") (pintype "input"))
    )
    (net (code "54") (name "/PD0") (class "Default")
      (node (ref "C19") (pin "2") (pinfunction "2_2") (pintype "input"))
      (node (ref "U1") (pin "5") (pinfunction "PD0-OSC_IN_5") (pintype "input"))
      (node (ref "X2") (pin "1") (pinfunction "OSC1_1") (pintype "input"))
    )
    (net (code "55") (name "/PD1") (class "Default")
      (node (ref "C18") (pin "2") (pinfunction "2_2") (pintype "input"))
      (node (ref "U1") (pin "6") (pinfunction "PD1-OSC_OUT_6") (pintype "input"))
      (node (ref "X2") (pin "2") (pinfunction "OSC2_2") (pintype "input"))
    )
    (net (code "56") (name "/PD2") (class "Default")
      (node (ref "H2") (pin "8") (pinfunction "8_8") (pintype "input"))
      (node (ref "U1") (pin "54") (pinfunction "PD2_54") (pintype "input"))
    )
    (net (code "57") (name "/RTS") (class "Default")
      (node (ref "Q2") (pin "2") (pinfunction "E_2") (pintype "input"))
      (node (ref "R22") (pin "1") (pinfunction "1_1") (pintype "input"))
      (node (ref "U3") (pin "14") (pinfunction "RTS#_14") (pintype "input"))
    )
    (net (code "58") (name "3V3") (class "Default")
      (node (ref "C1") (pin "1") (pinfunction "1_1") (pintype "input"))
      (node (ref "C16") (pin "1") (pinfunction "1_1") (pintype "input"))
      (node (ref "C20") (pin "1") (pinfunction "1_1") (pintype "input"))
      (node (ref "C23") (pin "2") (pinfunction "2_2") (pintype "input"))
      (node (ref "C3") (pin "2") (pinfunction "2_2") (pintype "input"))
      (node (ref "C4") (pin "1") (pinfunction "1_1") (pintype "input"))
      (node (ref "C5") (pin "1") (pinfunction "1_1") (pintype "input"))
      (node (ref "C6") (pin "1") (pinfunction "1_1") (pintype "input"))
      (node (ref "C7") (pin "2") (pinfunction "2_2") (pintype "input"))
      (node (ref "D1") (pin "1") (pinfunction "K_1") (pintype "input"))
      (node (ref "H1") (pin "26") (pinfunction "26_26") (pintype "input"))
      (node (ref "H1") (pin "28") (pinfunction "28_28") (pintype "input"))
      (node (ref "H1") (pin "30") (pinfunction "30_30") (pintype "input"))
      (node (ref "H3") (pin "4") (pinfunction "4_4") (pintype "input"))
      (node (ref "LED1") (pin "1") (pinfunction "A_1") (pintype "input"))
      (node (ref "LED2") (pin "1") (pinfunction "A_1") (pintype "input"))
      (node (ref "Q1") (pin "2") (pinfunction "E_2") (pintype "input"))
      (node (ref "R26") (pin "2") (pinfunction "2_2") (pintype "input"))
      (node (ref "R28") (pin "2") (pinfunction "2_2") (pintype "input"))
      (node (ref "R30") (pin "2") (pinfunction "2_2") (pintype "input"))
      (node (ref "R32") (pin "2") (pinfunction "2_2") (pintype "input"))
      (node (ref "R33") (pin "1") (pinfunction "1_1") (pintype "input"))
      (node (ref "U1") (pin "1") (pinfunction "VBAT_1") (pintype "input"))
      (node (ref "U1") (pin "13") (pinfunction "VDDA_13") (pintype "input"))
      (node (ref "U1") (pin "19") (pinfunction "VDD_4_19") (pintype "input"))
      (node (ref "U1") (pin "32") (pinfunction "VDD_1_32") (pintype "input"))
      (node (ref "U1") (pin "48") (pinfunction "VDD_2_48") (pintype "input"))
      (node (ref "U1") (pin "64") (pinfunction "VDD_3_64") (pintype "input"))
      (node (ref "U4") (pin "4") (pinfunction "VOUT_4") (pintype "input"))
      (node (ref "U5") (pin "3") (pinfunction "VCC_3") (pintype "input"))
      (node (ref "U7") (pin "13") (pinfunction "VDD_13") (pintype "input"))
      (node (ref "U7") (pin "8") (pinfunction "VLOGIC_8") (pintype "input"))
    )
    (net (code "59") (name "5V") (class "Default")
      (node (ref "C15") (pin "1") (pinfunction "1_1") (pintype "input"))
      (node (ref "C2") (pin "1") (pinfunction "1_1") (pintype "input"))
      (node (ref "D2") (pin "1") (pinfunction "K_1") (pintype "input"))
      (node (ref "H1") (pin "1") (pinfunction "1_1") (pintype "input"))
      (node (ref "H1") (pin "2") (pinfunction "2_2") (pintype "input"))
      (node (ref "H2") (pin "29") (pinfunction "29_29") (pintype "input"))
      (node (ref "H2") (pin "30") (pinfunction "30_30") (pintype "input"))
      (node (ref "U3") (pin "16") (pinfunction "VCC_16") (pintype "input"))
      (node (ref "U4") (pin "3") (pinfunction "VIN_3") (pintype "input"))
      (node (ref "USB5") (pin "1") (pinfunction "VCC_1") (pintype "input"))
    )
    (net (code "60") (name "GND") (class "Default")
      (node (ref "C1") (pin "2") (pinfunction "2_2") (pintype "input"))
      (node (ref "C12") (pin "2") (pinfunction "2_2") (pintype "input"))
      (node (ref "C13") (pin "1") (pinfunction "1_1") (pintype "input"))
      (node (ref "C14") (pin "1") (pinfunction "1_1") (pintype "input"))
      (node (ref "C15") (pin "2") (pinfunction "2_2") (pintype "input"))
      (node (ref "C16") (pin "2") (pinfunction "2_2") (pintype "input"))
      (node (ref "C17") (pin "2") (pinfunction "2_2") (pintype "input"))
      (node (ref "C18") (pin "1") (pinfunction "1_1") (pintype "input"))
      (node (ref "C19") (pin "1") (pinfunction "1_1") (pintype "input"))
      (node (ref "C2") (pin "2") (pinfunction "2_2") (pintype "input"))
      (node (ref "C20") (pin "2") (pinfunction "2_2") (pintype "input"))
      (node (ref "C21") (pin "1") (pinfunction "1_1") (pintype "input"))
      (node (ref "C22") (pin "2") (pinfunction "2_2") (pintype "input"))
      (node (ref "C23") (pin "1") (pinfunction "1_1") (pintype "input"))
      (node (ref "C3") (pin "1") (pinfunction "1_1") (pintype "input"))
      (node (ref "C4") (pin "2") (pinfunction "2_2") (pintype "input"))
      (node (ref "C5") (pin "2") (pinfunction "2_2") (pintype "input"))
      (node (ref "C6") (pin "2") (pinfunction "2_2") (pintype "input"))
      (node (ref "C7") (pin "1") (pinfunction "1_1") (pintype "input"))
      (node (ref "D1") (pin "2") (pinfunction "A_2") (pintype "input"))
      (node (ref "D2") (pin "2") (pinfunction "A_2") (pintype "input"))
      (node (ref "F2") (pin "1") (pinfunction "1_1") (pintype "input"))
      (node (ref "H1") (pin "25") (pinfunction "25_25") (pintype "input"))
      (node (ref "H1") (pin "27") (pinfunction "27_27") (pintype "input"))
      (node (ref "H1") (pin "29") (pinfunction "29_29") (pintype "input"))
      (node (ref "H3") (pin "2") (pinfunction "2_2") (pintype "input"))
      (node (ref "R2") (pin "1") (pinfunction "1_1") (pintype "input"))
      (node (ref "R20") (pin "2") (pinfunction "2_2") (pintype "input"))
      (node (ref "R27") (pin "1") (pinfunction "1_1") (pintype "input"))
      (node (ref "R29") (pin "1") (pinfunction "1_1") (pintype "input"))
      (node (ref "R31") (pin "2") (pinfunction "2_2") (pintype "input"))
      (node (ref "R4") (pin "2") (pinfunction "2_2") (pintype "input"))
      (node (ref "SW1") (pin "2") (pinfunction "2_2") (pintype "input"))
      (node (ref "SW2") (pin "1") (pinfunction "1_1") (pintype "input"))
      (node (ref "U1") (pin "12") (pinfunction "VSSA_12") (pintype "input"))
      (node (ref "U1") (pin "18") (pinfunction "VSS_4_18") (pintype "input"))
      (node (ref "U1") (pin "63") (pinfunction "VSS_3_63") (pintype "input"))
      (node (ref "U3") (pin "1") (pinfunction "GND_1") (pintype "input"))
      (node (ref "U4") (pin "1") (pinfunction "GND_1") (pintype "input"))
      (node (ref "U5") (pin "2") (pinfunction "GND_2") (pintype "input"))
      (node (ref "U5") (pin "8") (pinfunction "S_8") (pintype "input"))
      (node (ref "U7") (pin "1") (pinfunction "CLKIN_1") (pintype "input"))
      (node (ref "U7") (pin "11") (pinfunction "FSYNC_11") (pintype "input"))
      (node (ref "U7") (pin "18") (pinfunction "GND_18") (pintype "input"))
      (node (ref "U7") (pin "25") (pinfunction "GND_25") (pintype "input"))
      (node (ref "USB5") (pin "6") (pinfunction "EH_6") (pintype "input"))
    )
    (net (code "61") (name "Net-(D4-C)") (class "Default")
      (node (ref "D4") (pin "1") (pinfunction "C_1") (pintype "input"))
      (node (ref "Q2") (pin "3") (pinfunction "C_3") (pintype "input"))
      (node (ref "R32") (pin "1") (pinfunction "1_1") (pintype "input"))
    )
    (net (code "62") (name "Net-(LED1-K)") (class "Default")
      (node (ref "LED1") (pin "2") (pinfunction "K_2") (pintype "input"))
      (node (ref "R21") (pin "1") (pinfunction "1_1") (pintype "input"))
    )
    (net (code "63") (name "Net-(LED2-K)") (class "Default")
      (node (ref "LED2") (pin "2") (pinfunction "K_2") (pintype "input"))
      (node (ref "R20") (pin "1") (pinfunction "1_1") (pintype "input"))
    )
    (net (code "64") (name "Net-(Q1-B)") (class "Default")
      (node (ref "Q1") (pin "1") (pinfunction "B_1") (pintype "input"))
      (node (ref "R22") (pin "2") (pinfunction "2_2") (pintype "input"))
    )
    (net (code "65") (name "Net-(Q1-C)") (class "Default")
      (node (ref "Q1") (pin "3") (pinfunction "C_3") (pintype "input"))
      (node (ref "R25") (pin "1") (pinfunction "1_1") (pintype "input"))
    )
    (net (code "66") (name "Net-(Q2-B)") (class "Default")
      (node (ref "Q2") (pin "1") (pinfunction "B_1") (pintype "input"))
      (node (ref "R23") (pin "2") (pinfunction "2_2") (pintype "input"))
    )
    (net (code "67") (name "Net-(R33-Pad2)") (class "Default")
      (node (ref "R33") (pin "2") (pinfunction "2_2") (pintype "input"))
      (node (ref "SW1") (pin "1") (pinfunction "1_1") (pintype "input"))
    )
    (net (code "68") (name "Net-(U1-VSS_1)") (class "Default")
      (node (ref "R2") (pin "2") (pinfunction "2_2") (pintype "input"))
      (node (ref "U1") (pin "31") (pinfunction "VSS_1_31") (pintype "input"))
    )
    (net (code "69") (name "Net-(U1-VSS_2)") (class "Default")
      (node (ref "R4") (pin "1") (pinfunction "1_1") (pintype "input"))
      (node (ref "U1") (pin "47") (pinfunction "VSS_2_47") (pintype "input"))
    )
    (net (code "70") (name "Net-(U3-UD+)") (class "Default")
      (node (ref "U3") (pin "5") (pinfunction "UD+_5") (pintype "input"))
      (node (ref "USB5") (pin "3") (pinfunction "D+_3") (pintype "input"))
    )
    (net (code "71") (name "Net-(U3-UD-)") (class "Default")
      (node (ref "U3") (pin "6") (pinfunction "UD-_6") (pintype "input"))
      (node (ref "USB5") (pin "2") (pinfunction "D-_2") (pintype "input"))
    )
    (net (code "72") (name "Net-(U3-V3)") (class "Default")
      (node (ref "C12") (pin "1") (pinfunction "1_1") (pintype "input"))
      (node (ref "U3") (pin "4") (pinfunction "V3_4") (pintype "input"))
    )
    (net (code "73") (name "Net-(U3-XI)") (class "Default")
      (node (ref "C13") (pin "2") (pinfunction "2_2") (pintype "input"))
      (node (ref "U3") (pin "7") (pinfunction "XI_7") (pintype "input"))
      (node (ref "X4") (pin "2") (pinfunction "2_2") (pintype "input"))
    )
    (net (code "74") (name "Net-(U3-XO)") (class "Default")
      (node (ref "C14") (pin "2") (pinfunction "2_2") (pintype "input"))
      (node (ref "U3") (pin "8") (pinfunction "XO_8") (pintype "input"))
      (node (ref "X4") (pin "1") (pinfunction "1_1") (pintype "input"))
    )
    (net (code "75") (name "Net-(U7-AD0)") (class "Default")
      (node (ref "R27") (pin "2") (pinfunction "2_2") (pintype "input"))
      (node (ref "U7") (pin "9") (pinfunction "AD0_9") (pintype "input"))
    )
    (net (code "76") (name "Net-(U7-CPOUT)") (class "Default")
      (node (ref "C21") (pin "2") (pinfunction "2_2") (pintype "input"))
      (node (ref "U7") (pin "20") (pinfunction "CPOUT_20") (pintype "input"))
    )
    (net (code "77") (name "Net-(U7-REGOUT)") (class "Default")
      (node (ref "C22") (pin "1") (pinfunction "1_1") (pintype "input"))
      (node (ref "U7") (pin "10") (pinfunction "REGOUT_10") (pintype "input"))
    )
    (net (code "78") (name "Net-(USB5-GND)") (class "Default")
      (node (ref "F2") (pin "2") (pinfunction "2_2") (pintype "input"))
      (node (ref "USB5") (pin "5") (pinfunction "GND_5") (pintype "input"))
    )
    (net (code "79") (name "unconnected-(U3-CTS#-Pad9)") (class "Default")
      (node (ref "U3") (pin "9") (pinfunction "CTS#_9") (pintype "input+no_connect"))
    )
    (net (code "80") (name "unconnected-(U3-DCD#-Pad12)") (class "Default")
      (node (ref "U3") (pin "12") (pinfunction "DCD#_12") (pintype "input+no_connect"))
    )
    (net (code "81") (name "unconnected-(U3-DSR#-Pad10)") (class "Default")
      (node (ref "U3") (pin "10") (pinfunction "DSR#_10") (pintype "input+no_connect"))
    )
    (net (code "82") (name "unconnected-(U3-R232-Pad15)") (class "Default")
      (node (ref "U3") (pin "15") (pinfunction "R232_15") (pintype "input+no_connect"))
    )
    (net (code "83") (name "unconnected-(U3-RI#-Pad11)") (class "Default")
      (node (ref "U3") (pin "11") (pinfunction "RI#_11") (pintype "input+no_connect"))
    )
    (net (code "84") (name "unconnected-(U4-VOUT-Pad2)") (class "Default")
      (node (ref "U4") (pin "2") (pinfunction "VOUT_2") (pintype "input+no_connect"))
    )
    (net (code "85") (name "unconnected-(U5-VREF-Pad5)") (class "Default")
      (node (ref "U5") (pin "5") (pinfunction "VREF_5") (pintype "input+no_connect"))
    )
    (net (code "86") (name "unconnected-(U7-AUX_CL-Pad7)") (class "Default")
      (node (ref "U7") (pin "7") (pinfunction "AUX_CL_7") (pintype "input+no_connect"))
    )
    (net (code "87") (name "unconnected-(U7-AUX_DA-Pad6)") (class "Default")
      (node (ref "U7") (pin "6") (pinfunction "AUX_DA_6") (pintype "input+no_connect"))
    )
    (net (code "88") (name "unconnected-(U7-NC-Pad2)") (class "Default")
      (node (ref "U7") (pin "2") (pinfunction "NC_2") (pintype "input+no_connect"))
    )
    (net (code "89") (name "unconnected-(U7-NC-Pad3)") (class "Default")
      (node (ref "U7") (pin "3") (pinfunction "NC_3") (pintype "input+no_connect"))
    )
    (net (code "90") (name "unconnected-(U7-NC-Pad4)") (class "Default")
      (node (ref "U7") (pin "4") (pinfunction "NC_4") (pintype "input+no_connect"))
    )
    (net (code "91") (name "unconnected-(U7-NC-Pad5)") (class "Default")
      (node (ref "U7") (pin "5") (pinfunction "NC_5") (pintype "input+no_connect"))
    )
    (net (code "92") (name "unconnected-(U7-NC-Pad14)") (class "Default")
      (node (ref "U7") (pin "14") (pinfunction "NC_14") (pintype "input+no_connect"))
    )
    (net (code "93") (name "unconnected-(U7-NC-Pad15)") (class "Default")
      (node (ref "U7") (pin "15") (pinfunction "NC_15") (pintype "input+no_connect"))
    )
    (net (code "94") (name "unconnected-(U7-NC-Pad16)") (class "Default")
      (node (ref "U7") (pin "16") (pinfunction "NC_16") (pintype "input+no_connect"))
    )
    (net (code "95") (name "unconnected-(U7-NC-Pad17)") (class "Default")
      (node (ref "U7") (pin "17") (pinfunction "NC_17") (pintype "input+no_connect"))
    )
    (net (code "96") (name "unconnected-(U7-RESV-Pad19)") (class "Default")
      (node (ref "U7") (pin "19") (pinfunction "RESV_19") (pintype "input+no_connect"))
    )
    (net (code "97") (name "unconnected-(U7-RESV-Pad21)") (class "Default")
      (node (ref "U7") (pin "21") (pinfunction "RESV_21") (pintype "input+no_connect"))
    )
    (net (code "98") (name "unconnected-(U7-RESV-Pad22)") (class "Default")
      (node (ref "U7") (pin "22") (pinfunction "RESV_22") (pintype "input+no_connect"))
    )
    (net (code "99") (name "unconnected-(USB5-ID-Pad4)") (class "Default")
      (node (ref "USB5") (pin "4") (pinfunction "ID_4") (pintype "input+no_connect"))
    )
  )
)
